# as14120_x31_fpga_cypress.net
KiCad netlist of a schematic drawn in Altium Designer
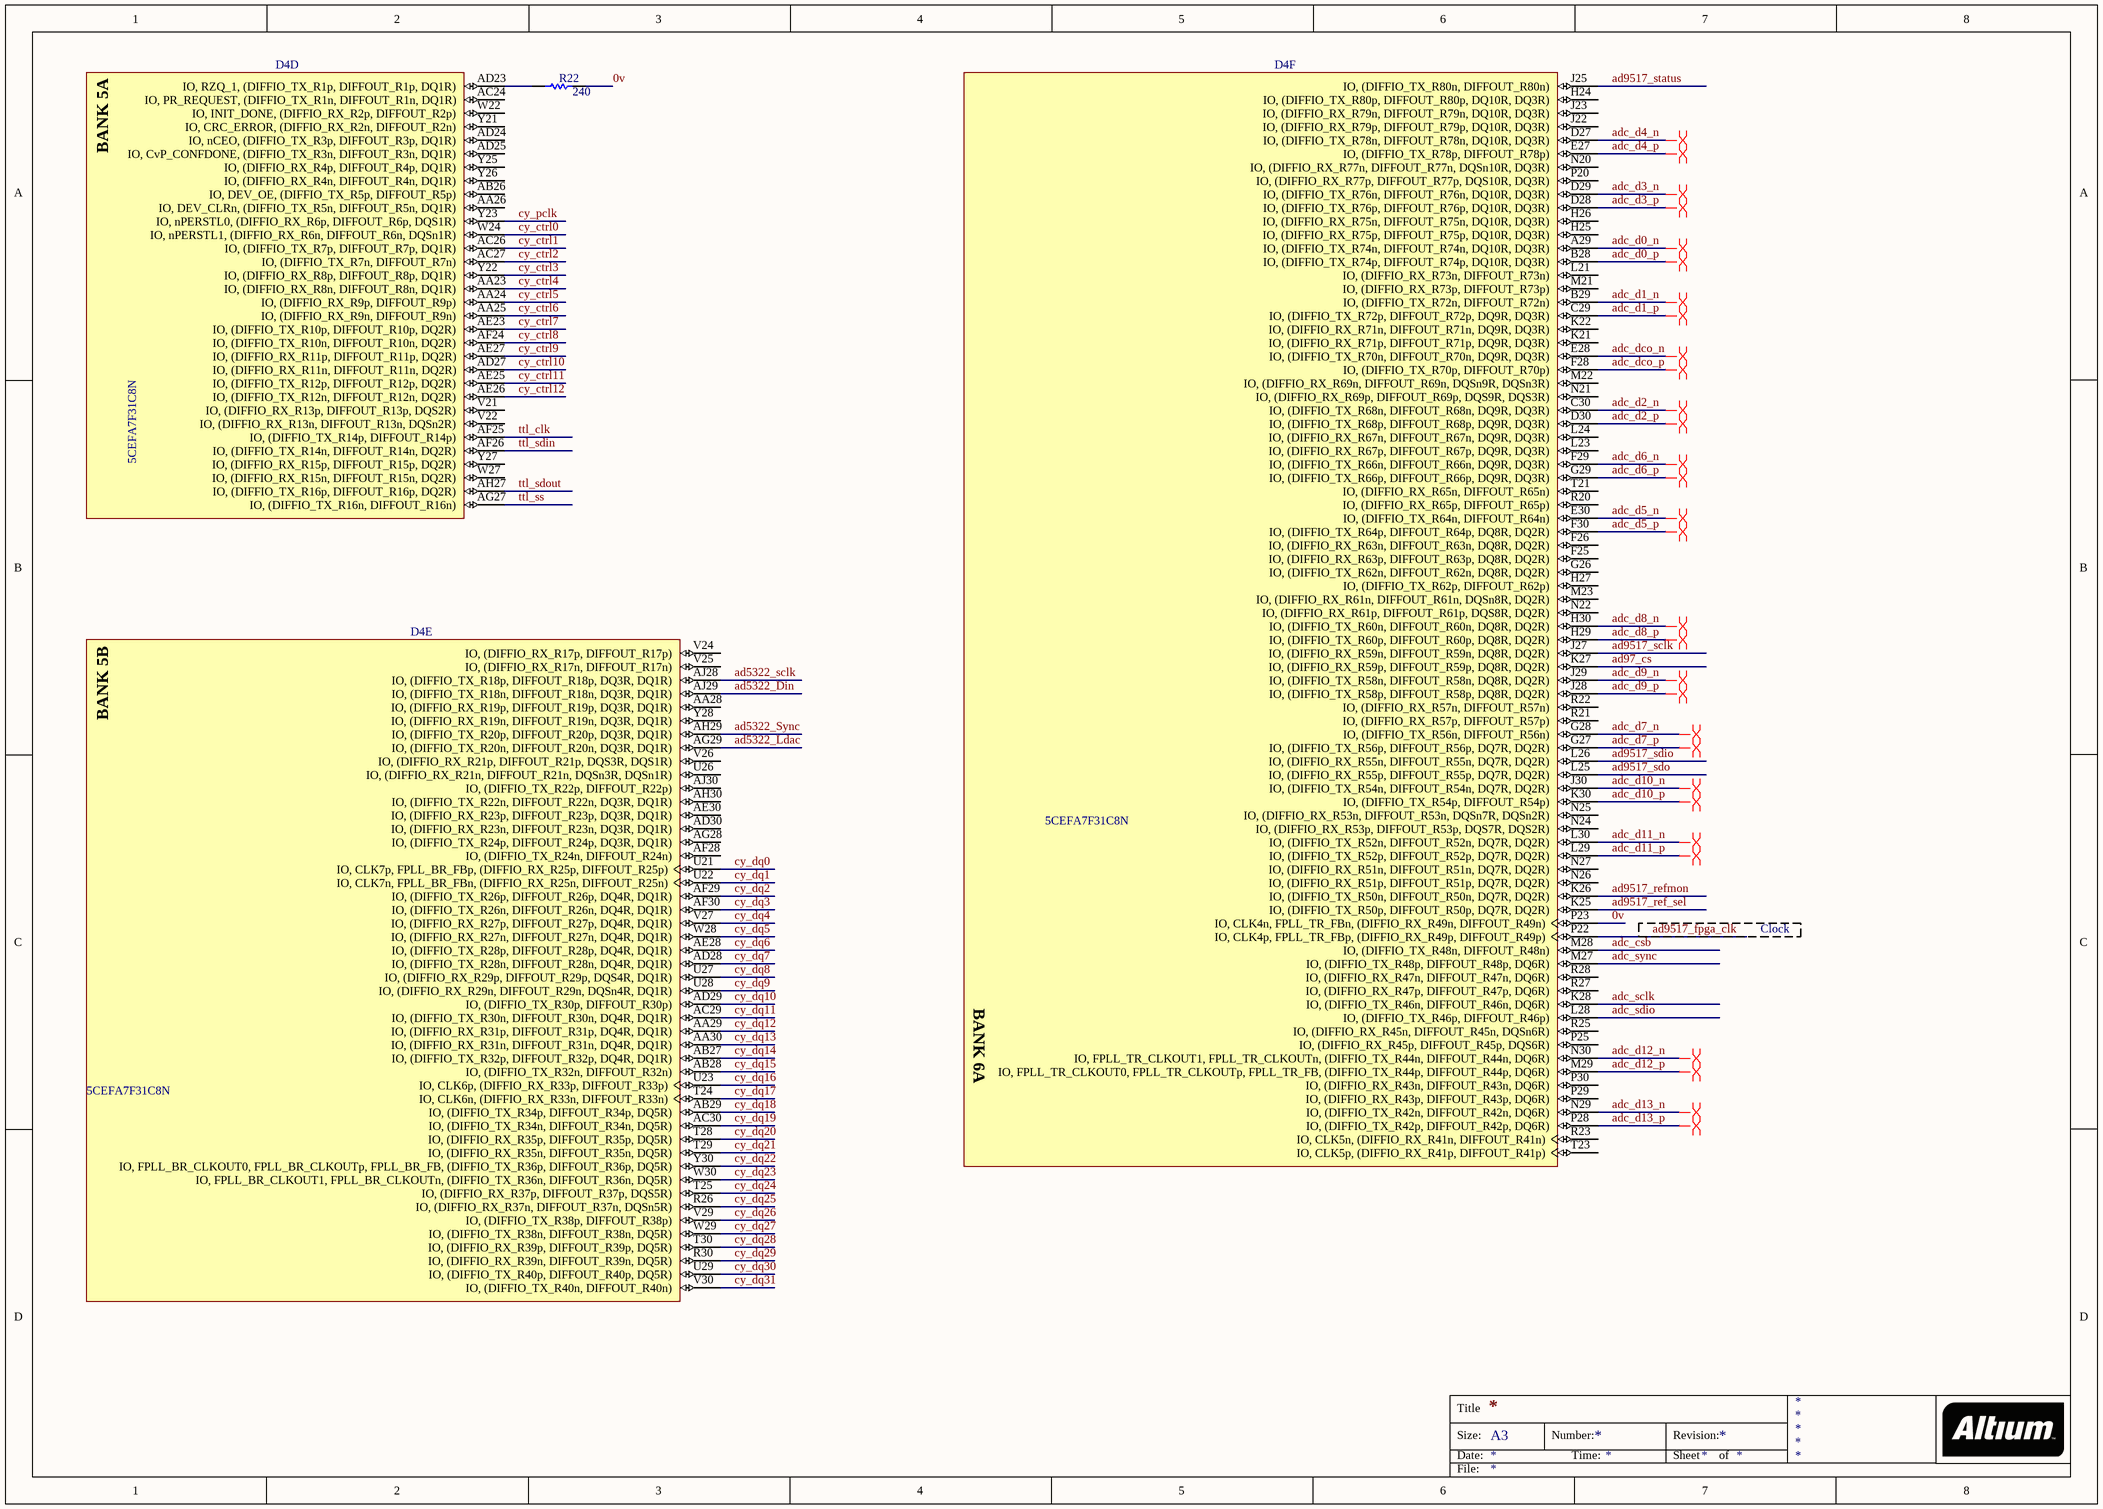
[diagram p0: as14120_x31_fpga_cypress.SchDoc]

(export (version "E")
  (design (tool "Eeschema 10.0.6"))
  (components
    (comp (ref "D4")
      (value "5CEFA7F31C8N")
      (footprint "ALTR-896-FBGA-2000A")
      (fields (field (name "MANUFACTURER") "Altera"))
      (libsource (lib "") (part "5CEFA7F31C8N_1"))
    )
    (comp (ref "R22")
      (value "240")
      (footprint "RESC0603(1608)_L")
      (description "1K 0.1W 5% 0603 (1608 Metric)  SMD")
      (fields (field (name "TOLERANCE") "5 %") (field (name "POWER") "0.1 W"))
      (libsource (lib "as14120") (part "RES_0603"))
    )
  )
  (nets
    (net (code "1") (name "/0v") (class "Default")
      (node (ref "D4") (pin "P23") (pinfunction "IO,_CLK4n,_FPLL_TR_FBn,_(DIFFIO_RX_R49n,_DIFFOUT_R49n)_P23") (pintype "bidirectional"))
      (node (ref "R22") (pin "2") (pinfunction "2_2") (pintype "passive"))
    )
    (net (code "2") (name "/ad97_cs") (class "Default")
      (node (ref "D4") (pin "K27") (pinfunction "IO,_(DIFFIO_RX_R59p,_DIFFOUT_R59p,_DQ8R,_DQ2R)_K27") (pintype "bidirectional"))
    )
    (net (code "3") (name "/ad5322_Din") (class "Default")
      (node (ref "D4") (pin "AJ29") (pinfunction "IO,_(DIFFIO_TX_R18n,_DIFFOUT_R18n,_DQ3R,_DQ1R)_AJ29") (pintype "bidirectional"))
    )
    (net (code "4") (name "/ad5322_Ldac") (class "Default")
      (node (ref "D4") (pin "AG29") (pinfunction "IO,_(DIFFIO_TX_R20n,_DIFFOUT_R20n,_DQ3R,_DQ1R)_AG29") (pintype "bidirectional"))
    )
    (net (code "5") (name "/ad5322_Sync") (class "Default")
      (node (ref "D4") (pin "AH29") (pinfunction "IO,_(DIFFIO_TX_R20p,_DIFFOUT_R20p,_DQ3R,_DQ1R)_AH29") (pintype "bidirectional"))
    )
    (net (code "6") (name "/ad5322_sclk") (class "Default")
      (node (ref "D4") (pin "AJ28") (pinfunction "IO,_(DIFFIO_TX_R18p,_DIFFOUT_R18p,_DQ3R,_DQ1R)_AJ28") (pintype "bidirectional"))
    )
    (net (code "7") (name "/ad9517_fpga_clk") (class "Default")
      (node (ref "D4") (pin "P22") (pinfunction "IO,_CLK4p,_FPLL_TR_FBp,_(DIFFIO_RX_R49p,_DIFFOUT_R49p)_P22") (pintype "bidirectional"))
    )
    (net (code "8") (name "/ad9517_ref_sel") (class "Default")
      (node (ref "D4") (pin "K25") (pinfunction "IO,_(DIFFIO_TX_R50p,_DIFFOUT_R50p,_DQ7R,_DQ2R)_K25") (pintype "bidirectional"))
    )
    (net (code "9") (name "/ad9517_refmon") (class "Default")
      (node (ref "D4") (pin "K26") (pinfunction "IO,_(DIFFIO_TX_R50n,_DIFFOUT_R50n,_DQ7R,_DQ2R)_K26") (pintype "bidirectional"))
    )
    (net (code "10") (name "/ad9517_sclk") (class "Default")
      (node (ref "D4") (pin "J27") (pinfunction "IO,_(DIFFIO_RX_R59n,_DIFFOUT_R59n,_DQ8R,_DQ2R)_J27") (pintype "bidirectional"))
    )
    (net (code "11") (name "/ad9517_sdio") (class "Default")
      (node (ref "D4") (pin "L26") (pinfunction "IO,_(DIFFIO_RX_R55n,_DIFFOUT_R55n,_DQ7R,_DQ2R)_L26") (pintype "bidirectional"))
    )
    (net (code "12") (name "/ad9517_sdo") (class "Default")
      (node (ref "D4") (pin "L25") (pinfunction "IO,_(DIFFIO_RX_R55p,_DIFFOUT_R55p,_DQ7R,_DQ2R)_L25") (pintype "bidirectional"))
    )
    (net (code "13") (name "/ad9517_status") (class "Default")
      (node (ref "D4") (pin "J25") (pinfunction "IO,_(DIFFIO_TX_R80n,_DIFFOUT_R80n)_J25") (pintype "bidirectional"))
    )
    (net (code "14") (name "/adc_csb") (class "Default")
      (node (ref "D4") (pin "M28") (pinfunction "IO,_(DIFFIO_TX_R48n,_DIFFOUT_R48n)_M28") (pintype "bidirectional"))
    )
    (net (code "15") (name "/adc_d0_n") (class "Default")
      (node (ref "D4") (pin "A29") (pinfunction "IO,_(DIFFIO_TX_R74n,_DIFFOUT_R74n,_DQ10R,_DQ3R)_A29") (pintype "bidirectional"))
    )
    (net (code "16") (name "/adc_d0_p") (class "Default")
      (node (ref "D4") (pin "B28") (pinfunction "IO,_(DIFFIO_TX_R74p,_DIFFOUT_R74p,_DQ10R,_DQ3R)_B28") (pintype "bidirectional"))
    )
    (net (code "17") (name "/adc_d1_n") (class "Default")
      (node (ref "D4") (pin "B29") (pinfunction "IO,_(DIFFIO_TX_R72n,_DIFFOUT_R72n)_B29") (pintype "bidirectional"))
    )
    (net (code "18") (name "/adc_d1_p") (class "Default")
      (node (ref "D4") (pin "C29") (pinfunction "IO,_(DIFFIO_TX_R72p,_DIFFOUT_R72p,_DQ9R,_DQ3R)_C29") (pintype "bidirectional"))
    )
    (net (code "19") (name "/adc_d2_n") (class "Default")
      (node (ref "D4") (pin "C30") (pinfunction "IO,_(DIFFIO_TX_R68n,_DIFFOUT_R68n,_DQ9R,_DQ3R)_C30") (pintype "bidirectional"))
    )
    (net (code "20") (name "/adc_d2_p") (class "Default")
      (node (ref "D4") (pin "D30") (pinfunction "IO,_(DIFFIO_TX_R68p,_DIFFOUT_R68p,_DQ9R,_DQ3R)_D30") (pintype "bidirectional"))
    )
    (net (code "21") (name "/adc_d3_n") (class "Default")
      (node (ref "D4") (pin "D29") (pinfunction "IO,_(DIFFIO_TX_R76n,_DIFFOUT_R76n,_DQ10R,_DQ3R)_D29") (pintype "bidirectional"))
    )
    (net (code "22") (name "/adc_d3_p") (class "Default")
      (node (ref "D4") (pin "D28") (pinfunction "IO,_(DIFFIO_TX_R76p,_DIFFOUT_R76p,_DQ10R,_DQ3R)_D28") (pintype "bidirectional"))
    )
    (net (code "23") (name "/adc_d4_n") (class "Default")
      (node (ref "D4") (pin "D27") (pinfunction "IO,_(DIFFIO_TX_R78n,_DIFFOUT_R78n,_DQ10R,_DQ3R)_D27") (pintype "bidirectional"))
    )
    (net (code "24") (name "/adc_d4_p") (class "Default")
      (node (ref "D4") (pin "E27") (pinfunction "IO,_(DIFFIO_TX_R78p,_DIFFOUT_R78p)_E27") (pintype "bidirectional"))
    )
    (net (code "25") (name "/adc_d5_n") (class "Default")
      (node (ref "D4") (pin "E30") (pinfunction "IO,_(DIFFIO_TX_R64n,_DIFFOUT_R64n)_E30") (pintype "bidirectional"))
    )
    (net (code "26") (name "/adc_d5_p") (class "Default")
      (node (ref "D4") (pin "F30") (pinfunction "IO,_(DIFFIO_TX_R64p,_DIFFOUT_R64p,_DQ8R,_DQ2R)_F30") (pintype "bidirectional"))
    )
    (net (code "27") (name "/adc_d6_n") (class "Default")
      (node (ref "D4") (pin "F29") (pinfunction "IO,_(DIFFIO_TX_R66n,_DIFFOUT_R66n,_DQ9R,_DQ3R)_F29") (pintype "bidirectional"))
    )
    (net (code "28") (name "/adc_d6_p") (class "Default")
      (node (ref "D4") (pin "G29") (pinfunction "IO,_(DIFFIO_TX_R66p,_DIFFOUT_R66p,_DQ9R,_DQ3R)_G29") (pintype "bidirectional"))
    )
    (net (code "29") (name "/adc_d7_n") (class "Default")
      (node (ref "D4") (pin "G28") (pinfunction "IO,_(DIFFIO_TX_R56n,_DIFFOUT_R56n)_G28") (pintype "bidirectional"))
    )
    (net (code "30") (name "/adc_d7_p") (class "Default")
      (node (ref "D4") (pin "G27") (pinfunction "IO,_(DIFFIO_TX_R56p,_DIFFOUT_R56p,_DQ7R,_DQ2R)_G27") (pintype "bidirectional"))
    )
    (net (code "31") (name "/adc_d8_n") (class "Default")
      (node (ref "D4") (pin "H30") (pinfunction "IO,_(DIFFIO_TX_R60n,_DIFFOUT_R60n,_DQ8R,_DQ2R)_H30") (pintype "bidirectional"))
    )
    (net (code "32") (name "/adc_d8_p") (class "Default")
      (node (ref "D4") (pin "H29") (pinfunction "IO,_(DIFFIO_TX_R60p,_DIFFOUT_R60p,_DQ8R,_DQ2R)_H29") (pintype "bidirectional"))
    )
    (net (code "33") (name "/adc_d9_n") (class "Default")
      (node (ref "D4") (pin "J29") (pinfunction "IO,_(DIFFIO_TX_R58n,_DIFFOUT_R58n,_DQ8R,_DQ2R)_J29") (pintype "bidirectional"))
    )
    (net (code "34") (name "/adc_d9_p") (class "Default")
      (node (ref "D4") (pin "J28") (pinfunction "IO,_(DIFFIO_TX_R58p,_DIFFOUT_R58p,_DQ8R,_DQ2R)_J28") (pintype "bidirectional"))
    )
    (net (code "35") (name "/adc_d10_n") (class "Default")
      (node (ref "D4") (pin "J30") (pinfunction "IO,_(DIFFIO_TX_R54n,_DIFFOUT_R54n,_DQ7R,_DQ2R)_J30") (pintype "bidirectional"))
    )
    (net (code "36") (name "/adc_d10_p") (class "Default")
      (node (ref "D4") (pin "K30") (pinfunction "IO,_(DIFFIO_TX_R54p,_DIFFOUT_R54p)_K30") (pintype "bidirectional"))
    )
    (net (code "37") (name "/adc_d11_n") (class "Default")
      (node (ref "D4") (pin "L30") (pinfunction "IO,_(DIFFIO_TX_R52n,_DIFFOUT_R52n,_DQ7R,_DQ2R)_L30") (pintype "bidirectional"))
    )
    (net (code "38") (name "/adc_d11_p") (class "Default")
      (node (ref "D4") (pin "L29") (pinfunction "IO,_(DIFFIO_TX_R52p,_DIFFOUT_R52p,_DQ7R,_DQ2R)_L29") (pintype "bidirectional"))
    )
    (net (code "39") (name "/adc_d12_n") (class "Default")
      (node (ref "D4") (pin "N30") (pinfunction "IO,_FPLL_TR_CLKOUT1,_FPLL_TR_CLKOUTn,_(DIFFIO_TX_R44n,_DIFFOUT_R44n,_DQ6R)_N30") (pintype "bidirectional"))
    )
    (net (code "40") (name "/adc_d12_p") (class "Default")
      (node (ref "D4") (pin "M29") (pinfunction "IO,_FPLL_TR_CLKOUT0,_FPLL_TR_CLKOUTp,_FPLL_TR_FB,_(DIFFIO_TX_R44p,_DIFFOUT_R44p,_DQ6R)_M29") (pintype "bidirectional"))
    )
    (net (code "41") (name "/adc_d13_n") (class "Default")
      (node (ref "D4") (pin "N29") (pinfunction "IO,_(DIFFIO_TX_R42n,_DIFFOUT_R42n,_DQ6R)_N29") (pintype "bidirectional"))
    )
    (net (code "42") (name "/adc_d13_p") (class "Default")
      (node (ref "D4") (pin "P28") (pinfunction "IO,_(DIFFIO_TX_R42p,_DIFFOUT_R42p,_DQ6R)_P28") (pintype "bidirectional"))
    )
    (net (code "43") (name "/adc_dco_n") (class "Default")
      (node (ref "D4") (pin "E28") (pinfunction "IO,_(DIFFIO_TX_R70n,_DIFFOUT_R70n,_DQ9R,_DQ3R)_E28") (pintype "bidirectional"))
    )
    (net (code "44") (name "/adc_dco_p") (class "Default")
      (node (ref "D4") (pin "F28") (pinfunction "IO,_(DIFFIO_TX_R70p,_DIFFOUT_R70p)_F28") (pintype "bidirectional"))
    )
    (net (code "45") (name "/adc_sclk") (class "Default")
      (node (ref "D4") (pin "K28") (pinfunction "IO,_(DIFFIO_TX_R46n,_DIFFOUT_R46n,_DQ6R)_K28") (pintype "bidirectional"))
    )
    (net (code "46") (name "/adc_sdio") (class "Default")
      (node (ref "D4") (pin "L28") (pinfunction "IO,_(DIFFIO_TX_R46p,_DIFFOUT_R46p)_L28") (pintype "bidirectional"))
    )
    (net (code "47") (name "/adc_sync") (class "Default")
      (node (ref "D4") (pin "M27") (pinfunction "IO,_(DIFFIO_TX_R48p,_DIFFOUT_R48p,_DQ6R)_M27") (pintype "bidirectional"))
    )
    (net (code "48") (name "/cy_ctrl0") (class "Default")
      (node (ref "D4") (pin "W24") (pinfunction "IO,_nPERSTL1,_(DIFFIO_RX_R6n,_DIFFOUT_R6n,_DQSn1R)_W24") (pintype "bidirectional"))
    )
    (net (code "49") (name "/cy_ctrl1") (class "Default")
      (node (ref "D4") (pin "AC26") (pinfunction "IO,_(DIFFIO_TX_R7p,_DIFFOUT_R7p,_DQ1R)_AC26") (pintype "bidirectional"))
    )
    (net (code "50") (name "/cy_ctrl2") (class "Default")
      (node (ref "D4") (pin "AC27") (pinfunction "IO,_(DIFFIO_TX_R7n,_DIFFOUT_R7n)_AC27") (pintype "bidirectional"))
    )
    (net (code "51") (name "/cy_ctrl3") (class "Default")
      (node (ref "D4") (pin "Y22") (pinfunction "IO,_(DIFFIO_RX_R8p,_DIFFOUT_R8p,_DQ1R)_Y22") (pintype "bidirectional"))
    )
    (net (code "52") (name "/cy_ctrl4") (class "Default")
      (node (ref "D4") (pin "AA23") (pinfunction "IO,_(DIFFIO_RX_R8n,_DIFFOUT_R8n,_DQ1R)_AA23") (pintype "bidirectional"))
    )
    (net (code "53") (name "/cy_ctrl5") (class "Default")
      (node (ref "D4") (pin "AA24") (pinfunction "IO,_(DIFFIO_RX_R9p,_DIFFOUT_R9p)_AA24") (pintype "bidirectional"))
    )
    (net (code "54") (name "/cy_ctrl6") (class "Default")
      (node (ref "D4") (pin "AA25") (pinfunction "IO,_(DIFFIO_RX_R9n,_DIFFOUT_R9n)_AA25") (pintype "bidirectional"))
    )
    (net (code "55") (name "/cy_ctrl7") (class "Default")
      (node (ref "D4") (pin "AE23") (pinfunction "IO,_(DIFFIO_TX_R10p,_DIFFOUT_R10p,_DQ2R)_AE23") (pintype "bidirectional"))
    )
    (net (code "56") (name "/cy_ctrl8") (class "Default")
      (node (ref "D4") (pin "AF24") (pinfunction "IO,_(DIFFIO_TX_R10n,_DIFFOUT_R10n,_DQ2R)_AF24") (pintype "bidirectional"))
    )
    (net (code "57") (name "/cy_ctrl9") (class "Default")
      (node (ref "D4") (pin "AE27") (pinfunction "IO,_(DIFFIO_RX_R11p,_DIFFOUT_R11p,_DQ2R)_AE27") (pintype "bidirectional"))
    )
    (net (code "58") (name "/cy_ctrl10") (class "Default")
      (node (ref "D4") (pin "AD27") (pinfunction "IO,_(DIFFIO_RX_R11n,_DIFFOUT_R11n,_DQ2R)_AD27") (pintype "bidirectional"))
    )
    (net (code "59") (name "/cy_ctrl11") (class "Default")
      (node (ref "D4") (pin "AE25") (pinfunction "IO,_(DIFFIO_TX_R12p,_DIFFOUT_R12p,_DQ2R)_AE25") (pintype "bidirectional"))
    )
    (net (code "60") (name "/cy_ctrl12") (class "Default")
      (node (ref "D4") (pin "AE26") (pinfunction "IO,_(DIFFIO_TX_R12n,_DIFFOUT_R12n,_DQ2R)_AE26") (pintype "bidirectional"))
    )
    (net (code "61") (name "/cy_dq0") (class "Default")
      (node (ref "D4") (pin "U21") (pinfunction "IO,_CLK7p,_FPLL_BR_FBp,_(DIFFIO_RX_R25p,_DIFFOUT_R25p)_U21") (pintype "bidirectional"))
    )
    (net (code "62") (name "/cy_dq1") (class "Default")
      (node (ref "D4") (pin "U22") (pinfunction "IO,_CLK7n,_FPLL_BR_FBn,_(DIFFIO_RX_R25n,_DIFFOUT_R25n)_U22") (pintype "bidirectional"))
    )
    (net (code "63") (name "/cy_dq2") (class "Default")
      (node (ref "D4") (pin "AF29") (pinfunction "IO,_(DIFFIO_TX_R26p,_DIFFOUT_R26p,_DQ4R,_DQ1R)_AF29") (pintype "bidirectional"))
    )
    (net (code "64") (name "/cy_dq3") (class "Default")
      (node (ref "D4") (pin "AF30") (pinfunction "IO,_(DIFFIO_TX_R26n,_DIFFOUT_R26n,_DQ4R,_DQ1R)_AF30") (pintype "bidirectional"))
    )
    (net (code "65") (name "/cy_dq4") (class "Default")
      (node (ref "D4") (pin "V27") (pinfunction "IO,_(DIFFIO_RX_R27p,_DIFFOUT_R27p,_DQ4R,_DQ1R)_V27") (pintype "bidirectional"))
    )
    (net (code "66") (name "/cy_dq5") (class "Default")
      (node (ref "D4") (pin "W28") (pinfunction "IO,_(DIFFIO_RX_R27n,_DIFFOUT_R27n,_DQ4R,_DQ1R)_W28") (pintype "bidirectional"))
    )
    (net (code "67") (name "/cy_dq6") (class "Default")
      (node (ref "D4") (pin "AE28") (pinfunction "IO,_(DIFFIO_TX_R28p,_DIFFOUT_R28p,_DQ4R,_DQ1R)_AE28") (pintype "bidirectional"))
    )
    (net (code "68") (name "/cy_dq7") (class "Default")
      (node (ref "D4") (pin "AD28") (pinfunction "IO,_(DIFFIO_TX_R28n,_DIFFOUT_R28n,_DQ4R,_DQ1R)_AD28") (pintype "bidirectional"))
    )
    (net (code "69") (name "/cy_dq8") (class "Default")
      (node (ref "D4") (pin "U27") (pinfunction "IO,_(DIFFIO_RX_R29p,_DIFFOUT_R29p,_DQS4R,_DQ1R)_U27") (pintype "bidirectional"))
    )
    (net (code "70") (name "/cy_dq9") (class "Default")
      (node (ref "D4") (pin "U28") (pinfunction "IO,_(DIFFIO_RX_R29n,_DIFFOUT_R29n,_DQSn4R,_DQ1R)_U28") (pintype "bidirectional"))
    )
    (net (code "71") (name "/cy_dq10") (class "Default")
      (node (ref "D4") (pin "AD29") (pinfunction "IO,_(DIFFIO_TX_R30p,_DIFFOUT_R30p)_AD29") (pintype "bidirectional"))
    )
    (net (code "72") (name "/cy_dq11") (class "Default")
      (node (ref "D4") (pin "AC29") (pinfunction "IO,_(DIFFIO_TX_R30n,_DIFFOUT_R30n,_DQ4R,_DQ1R)_AC29") (pintype "bidirectional"))
    )
    (net (code "73") (name "/cy_dq12") (class "Default")
      (node (ref "D4") (pin "AA29") (pinfunction "IO,_(DIFFIO_RX_R31p,_DIFFOUT_R31p,_DQ4R,_DQ1R)_AA29") (pintype "bidirectional"))
    )
    (net (code "74") (name "/cy_dq13") (class "Default")
      (node (ref "D4") (pin "AA30") (pinfunction "IO,_(DIFFIO_RX_R31n,_DIFFOUT_R31n,_DQ4R,_DQ1R)_AA30") (pintype "bidirectional"))
    )
    (net (code "75") (name "/cy_dq14") (class "Default")
      (node (ref "D4") (pin "AB27") (pinfunction "IO,_(DIFFIO_TX_R32p,_DIFFOUT_R32p,_DQ4R,_DQ1R)_AB27") (pintype "bidirectional"))
    )
    (net (code "76") (name "/cy_dq15") (class "Default")
      (node (ref "D4") (pin "AB28") (pinfunction "IO,_(DIFFIO_TX_R32n,_DIFFOUT_R32n)_AB28") (pintype "bidirectional"))
    )
    (net (code "77") (name "/cy_dq16") (class "Default")
      (node (ref "D4") (pin "U23") (pinfunction "IO,_CLK6p,_(DIFFIO_RX_R33p,_DIFFOUT_R33p)_U23") (pintype "bidirectional"))
    )
    (net (code "78") (name "/cy_dq17") (class "Default")
      (node (ref "D4") (pin "T24") (pinfunction "IO,_CLK6n,_(DIFFIO_RX_R33n,_DIFFOUT_R33n)_T24") (pintype "bidirectional"))
    )
    (net (code "79") (name "/cy_dq18") (class "Default")
      (node (ref "D4") (pin "AB29") (pinfunction "IO,_(DIFFIO_TX_R34p,_DIFFOUT_R34p,_DQ5R)_AB29") (pintype "bidirectional"))
    )
    (net (code "80") (name "/cy_dq19") (class "Default")
      (node (ref "D4") (pin "AC30") (pinfunction "IO,_(DIFFIO_TX_R34n,_DIFFOUT_R34n,_DQ5R)_AC30") (pintype "bidirectional"))
    )
    (net (code "81") (name "/cy_dq20") (class "Default")
      (node (ref "D4") (pin "T28") (pinfunction "IO,_(DIFFIO_RX_R35p,_DIFFOUT_R35p,_DQ5R)_T28") (pintype "bidirectional"))
    )
    (net (code "82") (name "/cy_dq21") (class "Default")
      (node (ref "D4") (pin "T29") (pinfunction "IO,_(DIFFIO_RX_R35n,_DIFFOUT_R35n,_DQ5R)_T29") (pintype "bidirectional"))
    )
    (net (code "83") (name "/cy_dq22") (class "Default")
      (node (ref "D4") (pin "Y30") (pinfunction "IO,_FPLL_BR_CLKOUT0,_FPLL_BR_CLKOUTp,_FPLL_BR_FB,_(DIFFIO_TX_R36p,_DIFFOUT_R36p,_DQ5R)_Y30") (pintype "bidirectional"))
    )
    (net (code "84") (name "/cy_dq23") (class "Default")
      (node (ref "D4") (pin "W30") (pinfunction "IO,_FPLL_BR_CLKOUT1,_FPLL_BR_CLKOUTn,_(DIFFIO_TX_R36n,_DIFFOUT_R36n,_DQ5R)_W30") (pintype "bidirectional"))
    )
    (net (code "85") (name "/cy_dq24") (class "Default")
      (node (ref "D4") (pin "T25") (pinfunction "IO,_(DIFFIO_RX_R37p,_DIFFOUT_R37p,_DQS5R)_T25") (pintype "bidirectional"))
    )
    (net (code "86") (name "/cy_dq25") (class "Default")
      (node (ref "D4") (pin "R26") (pinfunction "IO,_(DIFFIO_RX_R37n,_DIFFOUT_R37n,_DQSn5R)_R26") (pintype "bidirectional"))
    )
    (net (code "87") (name "/cy_dq26") (class "Default")
      (node (ref "D4") (pin "V29") (pinfunction "IO,_(DIFFIO_TX_R38p,_DIFFOUT_R38p)_V29") (pintype "bidirectional"))
    )
    (net (code "88") (name "/cy_dq27") (class "Default")
      (node (ref "D4") (pin "W29") (pinfunction "IO,_(DIFFIO_TX_R38n,_DIFFOUT_R38n,_DQ5R)_W29") (pintype "bidirectional"))
    )
    (net (code "89") (name "/cy_dq28") (class "Default")
      (node (ref "D4") (pin "T30") (pinfunction "IO,_(DIFFIO_RX_R39p,_DIFFOUT_R39p,_DQ5R)_T30") (pintype "bidirectional"))
    )
    (net (code "90") (name "/cy_dq29") (class "Default")
      (node (ref "D4") (pin "R30") (pinfunction "IO,_(DIFFIO_RX_R39n,_DIFFOUT_R39n,_DQ5R)_R30") (pintype "bidirectional"))
    )
    (net (code "91") (name "/cy_dq30") (class "Default")
      (node (ref "D4") (pin "U29") (pinfunction "IO,_(DIFFIO_TX_R40p,_DIFFOUT_R40p,_DQ5R)_U29") (pintype "bidirectional"))
    )
    (net (code "92") (name "/cy_dq31") (class "Default")
      (node (ref "D4") (pin "V30") (pinfunction "IO,_(DIFFIO_TX_R40n,_DIFFOUT_R40n)_V30") (pintype "bidirectional"))
    )
    (net (code "93") (name "/cy_pclk") (class "Default")
      (node (ref "D4") (pin "Y23") (pinfunction "IO,_nPERSTL0,_(DIFFIO_RX_R6p,_DIFFOUT_R6p,_DQS1R)_Y23") (pintype "bidirectional"))
    )
    (net (code "94") (name "/ttl_clk") (class "Default")
      (node (ref "D4") (pin "AF25") (pinfunction "IO,_(DIFFIO_TX_R14p,_DIFFOUT_R14p)_AF25") (pintype "bidirectional"))
    )
    (net (code "95") (name "/ttl_sdin") (class "Default")
      (node (ref "D4") (pin "AF26") (pinfunction "IO,_(DIFFIO_TX_R14n,_DIFFOUT_R14n,_DQ2R)_AF26") (pintype "bidirectional"))
    )
    (net (code "96") (name "/ttl_sdout") (class "Default")
      (node (ref "D4") (pin "AH27") (pinfunction "IO,_(DIFFIO_TX_R16p,_DIFFOUT_R16p,_DQ2R)_AH27") (pintype "bidirectional"))
    )
    (net (code "97") (name "/ttl_ss") (class "Default")
      (node (ref "D4") (pin "AG27") (pinfunction "IO,_(DIFFIO_TX_R16n,_DIFFOUT_R16n)_AG27") (pintype "bidirectional"))
    )
    (net (code "98") (name "Net-(D4D-IO,_RZQ_1,_(DIFFIO_TX_R1p,_DIFFOUT_R1p,_DQ1R))") (class "Default")
      (node (ref "D4") (pin "AD23") (pinfunction "IO,_RZQ_1,_(DIFFIO_TX_R1p,_DIFFOUT_R1p,_DQ1R)_AD23") (pintype "bidirectional"))
      (node (ref "R22") (pin "1") (pinfunction "1_1") (pintype "passive"))
    )
    (net (code "99") (name "unconnected-(D4D-IO,_(DIFFIO_RX_R4n,_DIFFOUT_R4n,_DQ1R)-PadY26)") (class "Default")
      (node (ref "D4") (pin "Y26") (pinfunction "IO,_(DIFFIO_RX_R4n,_DIFFOUT_R4n,_DQ1R)_Y26") (pintype "bidirectional"))
    )
    (net (code "100") (name "unconnected-(D4D-IO,_(DIFFIO_RX_R4p,_DIFFOUT_R4p,_DQ1R)-PadY25)") (class "Default")
      (node (ref "D4") (pin "Y25") (pinfunction "IO,_(DIFFIO_RX_R4p,_DIFFOUT_R4p,_DQ1R)_Y25") (pintype "bidirectional"))
    )
    (net (code "101") (name "unconnected-(D4D-IO,_(DIFFIO_RX_R13n,_DIFFOUT_R13n,_DQSn2R)-PadV22)") (class "Default")
      (node (ref "D4") (pin "V22") (pinfunction "IO,_(DIFFIO_RX_R13n,_DIFFOUT_R13n,_DQSn2R)_V22") (pintype "bidirectional"))
    )
    (net (code "102") (name "unconnected-(D4D-IO,_(DIFFIO_RX_R13p,_DIFFOUT_R13p,_DQS2R)-PadV21)") (class "Default")
      (node (ref "D4") (pin "V21") (pinfunction "IO,_(DIFFIO_RX_R13p,_DIFFOUT_R13p,_DQS2R)_V21") (pintype "bidirectional"))
    )
    (net (code "103") (name "unconnected-(D4D-IO,_(DIFFIO_RX_R15n,_DIFFOUT_R15n,_DQ2R)-PadW27)") (class "Default")
      (node (ref "D4") (pin "W27") (pinfunction "IO,_(DIFFIO_RX_R15n,_DIFFOUT_R15n,_DQ2R)_W27") (pintype "bidirectional"))
    )
    (net (code "104") (name "unconnected-(D4D-IO,_(DIFFIO_RX_R15p,_DIFFOUT_R15p,_DQ2R)-PadY27)") (class "Default")
      (node (ref "D4") (pin "Y27") (pinfunction "IO,_(DIFFIO_RX_R15p,_DIFFOUT_R15p,_DQ2R)_Y27") (pintype "bidirectional"))
    )
    (net (code "105") (name "unconnected-(D4D-IO,_CRC_ERROR,_(DIFFIO_RX_R2n,_DIFFOUT_R2n)-PadY21)") (class "Default")
      (node (ref "D4") (pin "Y21") (pinfunction "IO,_CRC_ERROR,_(DIFFIO_RX_R2n,_DIFFOUT_R2n)_Y21") (pintype "bidirectional"))
    )
    (net (code "106") (name "unconnected-(D4D-IO,_CvP_CONFDONE,_(DIFFIO_TX_R3n,_DIFFOUT_R3n,_DQ1R)-PadAD25)") (class "Default")
      (node (ref "D4") (pin "AD25") (pinfunction "IO,_CvP_CONFDONE,_(DIFFIO_TX_R3n,_DIFFOUT_R3n,_DQ1R)_AD25") (pintype "bidirectional"))
    )
    (net (code "107") (name "unconnected-(D4D-IO,_DEV_CLRn,_(DIFFIO_TX_R5n,_DIFFOUT_R5n,_DQ1R)-PadAA26)") (class "Default")
      (node (ref "D4") (pin "AA26") (pinfunction "IO,_DEV_CLRn,_(DIFFIO_TX_R5n,_DIFFOUT_R5n,_DQ1R)_AA26") (pintype "bidirectional"))
    )
    (net (code "108") (name "unconnected-(D4D-IO,_DEV_OE,_(DIFFIO_TX_R5p,_DIFFOUT_R5p)-PadAB26)") (class "Default")
      (node (ref "D4") (pin "AB26") (pinfunction "IO,_DEV_OE,_(DIFFIO_TX_R5p,_DIFFOUT_R5p)_AB26") (pintype "bidirectional"))
    )
    (net (code "109") (name "unconnected-(D4D-IO,_INIT_DONE,_(DIFFIO_RX_R2p,_DIFFOUT_R2p)-PadW22)") (class "Default")
      (node (ref "D4") (pin "W22") (pinfunction "IO,_INIT_DONE,_(DIFFIO_RX_R2p,_DIFFOUT_R2p)_W22") (pintype "bidirectional"))
    )
    (net (code "110") (name "unconnected-(D4D-IO,_PR_REQUEST,_(DIFFIO_TX_R1n,_DIFFOUT_R1n,_DQ1R)-PadAC24)") (class "Default")
      (node (ref "D4") (pin "AC24") (pinfunction "IO,_PR_REQUEST,_(DIFFIO_TX_R1n,_DIFFOUT_R1n,_DQ1R)_AC24") (pintype "bidirectional"))
    )
    (net (code "111") (name "unconnected-(D4D-IO,_nCEO,_(DIFFIO_TX_R3p,_DIFFOUT_R3p,_DQ1R)-PadAD24)") (class "Default")
      (node (ref "D4") (pin "AD24") (pinfunction "IO,_nCEO,_(DIFFIO_TX_R3p,_DIFFOUT_R3p,_DQ1R)_AD24") (pintype "bidirectional"))
    )
    (net (code "112") (name "unconnected-(D4E-IO,_(DIFFIO_RX_R17n,_DIFFOUT_R17n)-PadV25)") (class "Default")
      (node (ref "D4") (pin "V25") (pinfunction "IO,_(DIFFIO_RX_R17n,_DIFFOUT_R17n)_V25") (pintype "bidirectional"))
    )
    (net (code "113") (name "unconnected-(D4E-IO,_(DIFFIO_RX_R17p,_DIFFOUT_R17p)-PadV24)") (class "Default")
      (node (ref "D4") (pin "V24") (pinfunction "IO,_(DIFFIO_RX_R17p,_DIFFOUT_R17p)_V24") (pintype "bidirectional"))
    )
    (net (code "114") (name "unconnected-(D4E-IO,_(DIFFIO_RX_R19n,_DIFFOUT_R19n,_DQ3R,_DQ1R)-PadY28)") (class "Default")
      (node (ref "D4") (pin "Y28") (pinfunction "IO,_(DIFFIO_RX_R19n,_DIFFOUT_R19n,_DQ3R,_DQ1R)_Y28") (pintype "bidirectional"))
    )
    (net (code "115") (name "unconnected-(D4E-IO,_(DIFFIO_RX_R19p,_DIFFOUT_R19p,_DQ3R,_DQ1R)-PadAA28)") (class "Default")
      (node (ref "D4") (pin "AA28") (pinfunction "IO,_(DIFFIO_RX_R19p,_DIFFOUT_R19p,_DQ3R,_DQ1R)_AA28") (pintype "bidirectional"))
    )
    (net (code "116") (name "unconnected-(D4E-IO,_(DIFFIO_RX_R21n,_DIFFOUT_R21n,_DQSn3R,_DQSn1R)-PadU26)") (class "Default")
      (node (ref "D4") (pin "U26") (pinfunction "IO,_(DIFFIO_RX_R21n,_DIFFOUT_R21n,_DQSn3R,_DQSn1R)_U26") (pintype "bidirectional"))
    )
    (net (code "117") (name "unconnected-(D4E-IO,_(DIFFIO_RX_R21p,_DIFFOUT_R21p,_DQS3R,_DQS1R)-PadV26)") (class "Default")
      (node (ref "D4") (pin "V26") (pinfunction "IO,_(DIFFIO_RX_R21p,_DIFFOUT_R21p,_DQS3R,_DQS1R)_V26") (pintype "bidirectional"))
    )
    (net (code "118") (name "unconnected-(D4E-IO,_(DIFFIO_RX_R23n,_DIFFOUT_R23n,_DQ3R,_DQ1R)-PadAD30)") (class "Default")
      (node (ref "D4") (pin "AD30") (pinfunction "IO,_(DIFFIO_RX_R23n,_DIFFOUT_R23n,_DQ3R,_DQ1R)_AD30") (pintype "bidirectional"))
    )
    (net (code "119") (name "unconnected-(D4E-IO,_(DIFFIO_RX_R23p,_DIFFOUT_R23p,_DQ3R,_DQ1R)-PadAE30)") (class "Default")
      (node (ref "D4") (pin "AE30") (pinfunction "IO,_(DIFFIO_RX_R23p,_DIFFOUT_R23p,_DQ3R,_DQ1R)_AE30") (pintype "bidirectional"))
    )
    (net (code "120") (name "unconnected-(D4E-IO,_(DIFFIO_TX_R22n,_DIFFOUT_R22n,_DQ3R,_DQ1R)-PadAH30)") (class "Default")
      (node (ref "D4") (pin "AH30") (pinfunction "IO,_(DIFFIO_TX_R22n,_DIFFOUT_R22n,_DQ3R,_DQ1R)_AH30") (pintype "bidirectional"))
    )
    (net (code "121") (name "unconnected-(D4E-IO,_(DIFFIO_TX_R22p,_DIFFOUT_R22p)-PadAJ30)") (class "Default")
      (node (ref "D4") (pin "AJ30") (pinfunction "IO,_(DIFFIO_TX_R22p,_DIFFOUT_R22p)_AJ30") (pintype "bidirectional"))
    )
    (net (code "122") (name "unconnected-(D4E-IO,_(DIFFIO_TX_R24n,_DIFFOUT_R24n)-PadAF28)") (class "Default")
      (node (ref "D4") (pin "AF28") (pinfunction "IO,_(DIFFIO_TX_R24n,_DIFFOUT_R24n)_AF28") (pintype "bidirectional"))
    )
    (net (code "123") (name "unconnected-(D4E-IO,_(DIFFIO_TX_R24p,_DIFFOUT_R24p,_DQ3R,_DQ1R)-PadAG28)") (class "Default")
      (node (ref "D4") (pin "AG28") (pinfunction "IO,_(DIFFIO_TX_R24p,_DIFFOUT_R24p,_DQ3R,_DQ1R)_AG28") (pintype "bidirectional"))
    )
    (net (code "124") (name "unconnected-(D4F-IO,_(DIFFIO_RX_R43n,_DIFFOUT_R43n,_DQ6R)-PadP30)") (class "Default")
      (node (ref "D4") (pin "P30") (pinfunction "IO,_(DIFFIO_RX_R43n,_DIFFOUT_R43n,_DQ6R)_P30") (pintype "bidirectional"))
    )
    (net (code "125") (name "unconnected-(D4F-IO,_(DIFFIO_RX_R43p,_DIFFOUT_R43p,_DQ6R)-PadP29)") (class "Default")
      (node (ref "D4") (pin "P29") (pinfunction "IO,_(DIFFIO_RX_R43p,_DIFFOUT_R43p,_DQ6R)_P29") (pintype "bidirectional"))
    )
    (net (code "126") (name "unconnected-(D4F-IO,_(DIFFIO_RX_R45n,_DIFFOUT_R45n,_DQSn6R)-PadR25)") (class "Default")
      (node (ref "D4") (pin "R25") (pinfunction "IO,_(DIFFIO_RX_R45n,_DIFFOUT_R45n,_DQSn6R)_R25") (pintype "bidirectional"))
    )
    (net (code "127") (name "unconnected-(D4F-IO,_(DIFFIO_RX_R45p,_DIFFOUT_R45p,_DQS6R)-PadP25)") (class "Default")
      (node (ref "D4") (pin "P25") (pinfunction "IO,_(DIFFIO_RX_R45p,_DIFFOUT_R45p,_DQS6R)_P25") (pintype "bidirectional"))
    )
    (net (code "128") (name "unconnected-(D4F-IO,_(DIFFIO_RX_R47n,_DIFFOUT_R47n,_DQ6R)-PadR28)") (class "Default")
      (node (ref "D4") (pin "R28") (pinfunction "IO,_(DIFFIO_RX_R47n,_DIFFOUT_R47n,_DQ6R)_R28") (pintype "bidirectional"))
    )
    (net (code "129") (name "unconnected-(D4F-IO,_(DIFFIO_RX_R47p,_DIFFOUT_R47p,_DQ6R)-PadR27)") (class "Default")
      (node (ref "D4") (pin "R27") (pinfunction "IO,_(DIFFIO_RX_R47p,_DIFFOUT_R47p,_DQ6R)_R27") (pintype "bidirectional"))
    )
    (net (code "130") (name "unconnected-(D4F-IO,_(DIFFIO_RX_R51n,_DIFFOUT_R51n,_DQ7R,_DQ2R)-PadN27)") (class "Default")
      (node (ref "D4") (pin "N27") (pinfunction "IO,_(DIFFIO_RX_R51n,_DIFFOUT_R51n,_DQ7R,_DQ2R)_N27") (pintype "bidirectional"))
    )
    (net (code "131") (name "unconnected-(D4F-IO,_(DIFFIO_RX_R51p,_DIFFOUT_R51p,_DQ7R,_DQ2R)-PadN26)") (class "Default")
      (node (ref "D4") (pin "N26") (pinfunction "IO,_(DIFFIO_RX_R51p,_DIFFOUT_R51p,_DQ7R,_DQ2R)_N26") (pintype "bidirectional"))
    )
    (net (code "132") (name "unconnected-(D4F-IO,_(DIFFIO_RX_R53n,_DIFFOUT_R53n,_DQSn7R,_DQSn2R)-PadN25)") (class "Default")
      (node (ref "D4") (pin "N25") (pinfunction "IO,_(DIFFIO_RX_R53n,_DIFFOUT_R53n,_DQSn7R,_DQSn2R)_N25") (pintype "bidirectional"))
    )
    (net (code "133") (name "unconnected-(D4F-IO,_(DIFFIO_RX_R53p,_DIFFOUT_R53p,_DQS7R,_DQS2R)-PadN24)") (class "Default")
      (node (ref "D4") (pin "N24") (pinfunction "IO,_(DIFFIO_RX_R53p,_DIFFOUT_R53p,_DQS7R,_DQS2R)_N24") (pintype "bidirectional"))
    )
    (net (code "134") (name "unconnected-(D4F-IO,_(DIFFIO_RX_R57n,_DIFFOUT_R57n)-PadR22)") (class "Default")
      (node (ref "D4") (pin "R22") (pinfunction "IO,_(DIFFIO_RX_R57n,_DIFFOUT_R57n)_R22") (pintype "bidirectional"))
    )
    (net (code "135") (name "unconnected-(D4F-IO,_(DIFFIO_RX_R57p,_DIFFOUT_R57p)-PadR21)") (class "Default")
      (node (ref "D4") (pin "R21") (pinfunction "IO,_(DIFFIO_RX_R57p,_DIFFOUT_R57p)_R21") (pintype "bidirectional"))
    )
    (net (code "136") (name "unconnected-(D4F-IO,_(DIFFIO_RX_R61n,_DIFFOUT_R61n,_DQSn8R,_DQ2R)-PadM23)") (class "Default")
      (node (ref "D4") (pin "M23") (pinfunction "IO,_(DIFFIO_RX_R61n,_DIFFOUT_R61n,_DQSn8R,_DQ2R)_M23") (pintype "bidirectional"))
    )
    (net (code "137") (name "unconnected-(D4F-IO,_(DIFFIO_RX_R61p,_DIFFOUT_R61p,_DQS8R,_DQ2R)-PadN22)") (class "Default")
      (node (ref "D4") (pin "N22") (pinfunction "IO,_(DIFFIO_RX_R61p,_DIFFOUT_R61p,_DQS8R,_DQ2R)_N22") (pintype "bidirectional"))
    )
    (net (code "138") (name "unconnected-(D4F-IO,_(DIFFIO_RX_R63n,_DIFFOUT_R63n,_DQ8R,_DQ2R)-PadF26)") (class "Default")
      (node (ref "D4") (pin "F26") (pinfunction "IO,_(DIFFIO_RX_R63n,_DIFFOUT_R63n,_DQ8R,_DQ2R)_F26") (pintype "bidirectional"))
    )
    (net (code "139") (name "unconnected-(D4F-IO,_(DIFFIO_RX_R63p,_DIFFOUT_R63p,_DQ8R,_DQ2R)-PadF25)") (class "Default")
      (node (ref "D4") (pin "F25") (pinfunction "IO,_(DIFFIO_RX_R63p,_DIFFOUT_R63p,_DQ8R,_DQ2R)_F25") (pintype "bidirectional"))
    )
    (net (code "140") (name "unconnected-(D4F-IO,_(DIFFIO_RX_R65n,_DIFFOUT_R65n)-PadT21)") (class "Default")
      (node (ref "D4") (pin "T21") (pinfunction "IO,_(DIFFIO_RX_R65n,_DIFFOUT_R65n)_T21") (pintype "bidirectional"))
    )
    (net (code "141") (name "unconnected-(D4F-IO,_(DIFFIO_RX_R65p,_DIFFOUT_R65p)-PadR20)") (class "Default")
      (node (ref "D4") (pin "R20") (pinfunction "IO,_(DIFFIO_RX_R65p,_DIFFOUT_R65p)_R20") (pintype "bidirectional"))
    )
    (net (code "142") (name "unconnected-(D4F-IO,_(DIFFIO_RX_R67n,_DIFFOUT_R67n,_DQ9R,_DQ3R)-PadL24)") (class "Default")
      (node (ref "D4") (pin "L24") (pinfunction "IO,_(DIFFIO_RX_R67n,_DIFFOUT_R67n,_DQ9R,_DQ3R)_L24") (pintype "bidirectional"))
    )
    (net (code "143") (name "unconnected-(D4F-IO,_(DIFFIO_RX_R67p,_DIFFOUT_R67p,_DQ9R,_DQ3R)-PadL23)") (class "Default")
      (node (ref "D4") (pin "L23") (pinfunction "IO,_(DIFFIO_RX_R67p,_DIFFOUT_R67p,_DQ9R,_DQ3R)_L23") (pintype "bidirectional"))
    )
    (net (code "144") (name "unconnected-(D4F-IO,_(DIFFIO_RX_R69n,_DIFFOUT_R69n,_DQSn9R,_DQSn3R)-PadM22)") (class "Default")
      (node (ref "D4") (pin "M22") (pinfunction "IO,_(DIFFIO_RX_R69n,_DIFFOUT_R69n,_DQSn9R,_DQSn3R)_M22") (pintype "bidirectional"))
    )
    (net (code "145") (name "unconnected-(D4F-IO,_(DIFFIO_RX_R69p,_DIFFOUT_R69p,_DQS9R,_DQS3R)-PadN21)") (class "Default")
      (node (ref "D4") (pin "N21") (pinfunction "IO,_(DIFFIO_RX_R69p,_DIFFOUT_R69p,_DQS9R,_DQS3R)_N21") (pintype "bidirectional"))
    )
    (net (code "146") (name "unconnected-(D4F-IO,_(DIFFIO_RX_R71n,_DIFFOUT_R71n,_DQ9R,_DQ3R)-PadK22)") (class "Default")
      (node (ref "D4") (pin "K22") (pinfunction "IO,_(DIFFIO_RX_R71n,_DIFFOUT_R71n,_DQ9R,_DQ3R)_K22") (pintype "bidirectional"))
    )
    (net (code "147") (name "unconnected-(D4F-IO,_(DIFFIO_RX_R71p,_DIFFOUT_R71p,_DQ9R,_DQ3R)-PadK21)") (class "Default")
      (node (ref "D4") (pin "K21") (pinfunction "IO,_(DIFFIO_RX_R71p,_DIFFOUT_R71p,_DQ9R,_DQ3R)_K21") (pintype "bidirectional"))
    )
    (net (code "148") (name "unconnected-(D4F-IO,_(DIFFIO_RX_R73n,_DIFFOUT_R73n)-PadL21)") (class "Default")
      (node (ref "D4") (pin "L21") (pinfunction "IO,_(DIFFIO_RX_R73n,_DIFFOUT_R73n)_L21") (pintype "bidirectional"))
    )
    (net (code "149") (name "unconnected-(D4F-IO,_(DIFFIO_RX_R73p,_DIFFOUT_R73p)-PadM21)") (class "Default")
      (node (ref "D4") (pin "M21") (pinfunction "IO,_(DIFFIO_RX_R73p,_DIFFOUT_R73p)_M21") (pintype "bidirectional"))
    )
    (net (code "150") (name "unconnected-(D4F-IO,_(DIFFIO_RX_R75n,_DIFFOUT_R75n,_DQ10R,_DQ3R)-PadH26)") (class "Default")
      (node (ref "D4") (pin "H26") (pinfunction "IO,_(DIFFIO_RX_R75n,_DIFFOUT_R75n,_DQ10R,_DQ3R)_H26") (pintype "bidirectional"))
    )
    (net (code "151") (name "unconnected-(D4F-IO,_(DIFFIO_RX_R75p,_DIFFOUT_R75p,_DQ10R,_DQ3R)-PadH25)") (class "Default")
      (node (ref "D4") (pin "H25") (pinfunction "IO,_(DIFFIO_RX_R75p,_DIFFOUT_R75p,_DQ10R,_DQ3R)_H25") (pintype "bidirectional"))
    )
    (net (code "152") (name "unconnected-(D4F-IO,_(DIFFIO_RX_R77n,_DIFFOUT_R77n,_DQSn10R,_DQ3R)-PadN20)") (class "Default")
      (node (ref "D4") (pin "N20") (pinfunction "IO,_(DIFFIO_RX_R77n,_DIFFOUT_R77n,_DQSn10R,_DQ3R)_N20") (pintype "bidirectional"))
    )
    (net (code "153") (name "unconnected-(D4F-IO,_(DIFFIO_RX_R77p,_DIFFOUT_R77p,_DQS10R,_DQ3R)-PadP20)") (class "Default")
      (node (ref "D4") (pin "P20") (pinfunction "IO,_(DIFFIO_RX_R77p,_DIFFOUT_R77p,_DQS10R,_DQ3R)_P20") (pintype "bidirectional"))
    )
    (net (code "154") (name "unconnected-(D4F-IO,_(DIFFIO_RX_R79n,_DIFFOUT_R79n,_DQ10R,_DQ3R)-PadJ23)") (class "Default")
      (node (ref "D4") (pin "J23") (pinfunction "IO,_(DIFFIO_RX_R79n,_DIFFOUT_R79n,_DQ10R,_DQ3R)_J23") (pintype "bidirectional"))
    )
    (net (code "155") (name "unconnected-(D4F-IO,_(DIFFIO_RX_R79p,_DIFFOUT_R79p,_DQ10R,_DQ3R)-PadJ22)") (class "Default")
      (node (ref "D4") (pin "J22") (pinfunction "IO,_(DIFFIO_RX_R79p,_DIFFOUT_R79p,_DQ10R,_DQ3R)_J22") (pintype "bidirectional"))
    )
    (net (code "156") (name "unconnected-(D4F-IO,_(DIFFIO_TX_R62n,_DIFFOUT_R62n,_DQ8R,_DQ2R)-PadG26)") (class "Default")
      (node (ref "D4") (pin "G26") (pinfunction "IO,_(DIFFIO_TX_R62n,_DIFFOUT_R62n,_DQ8R,_DQ2R)_G26") (pintype "bidirectional"))
    )
    (net (code "157") (name "unconnected-(D4F-IO,_(DIFFIO_TX_R62p,_DIFFOUT_R62p)-PadH27)") (class "Default")
      (node (ref "D4") (pin "H27") (pinfunction "IO,_(DIFFIO_TX_R62p,_DIFFOUT_R62p)_H27") (pintype "bidirectional"))
    )
    (net (code "158") (name "unconnected-(D4F-IO,_(DIFFIO_TX_R80p,_DIFFOUT_R80p,_DQ10R,_DQ3R)-PadH24)") (class "Default")
      (node (ref "D4") (pin "H24") (pinfunction "IO,_(DIFFIO_TX_R80p,_DIFFOUT_R80p,_DQ10R,_DQ3R)_H24") (pintype "bidirectional"))
    )
    (net (code "159") (name "unconnected-(D4F-IO,_CLK5n,_(DIFFIO_RX_R41n,_DIFFOUT_R41n)-PadR23)") (class "Default")
      (node (ref "D4") (pin "R23") (pinfunction "IO,_CLK5n,_(DIFFIO_RX_R41n,_DIFFOUT_R41n)_R23") (pintype "bidirectional"))
    )
    (net (code "160") (name "unconnected-(D4F-IO,_CLK5p,_(DIFFIO_RX_R41p,_DIFFOUT_R41p)-PadT23)") (class "Default")
      (node (ref "D4") (pin "T23") (pinfunction "IO,_CLK5p,_(DIFFIO_RX_R41p,_DIFFOUT_R41p)_T23") (pintype "bidirectional"))
    )
  )
)
